# Power.net
KiCad netlist of a schematic drawn in Altium Designer
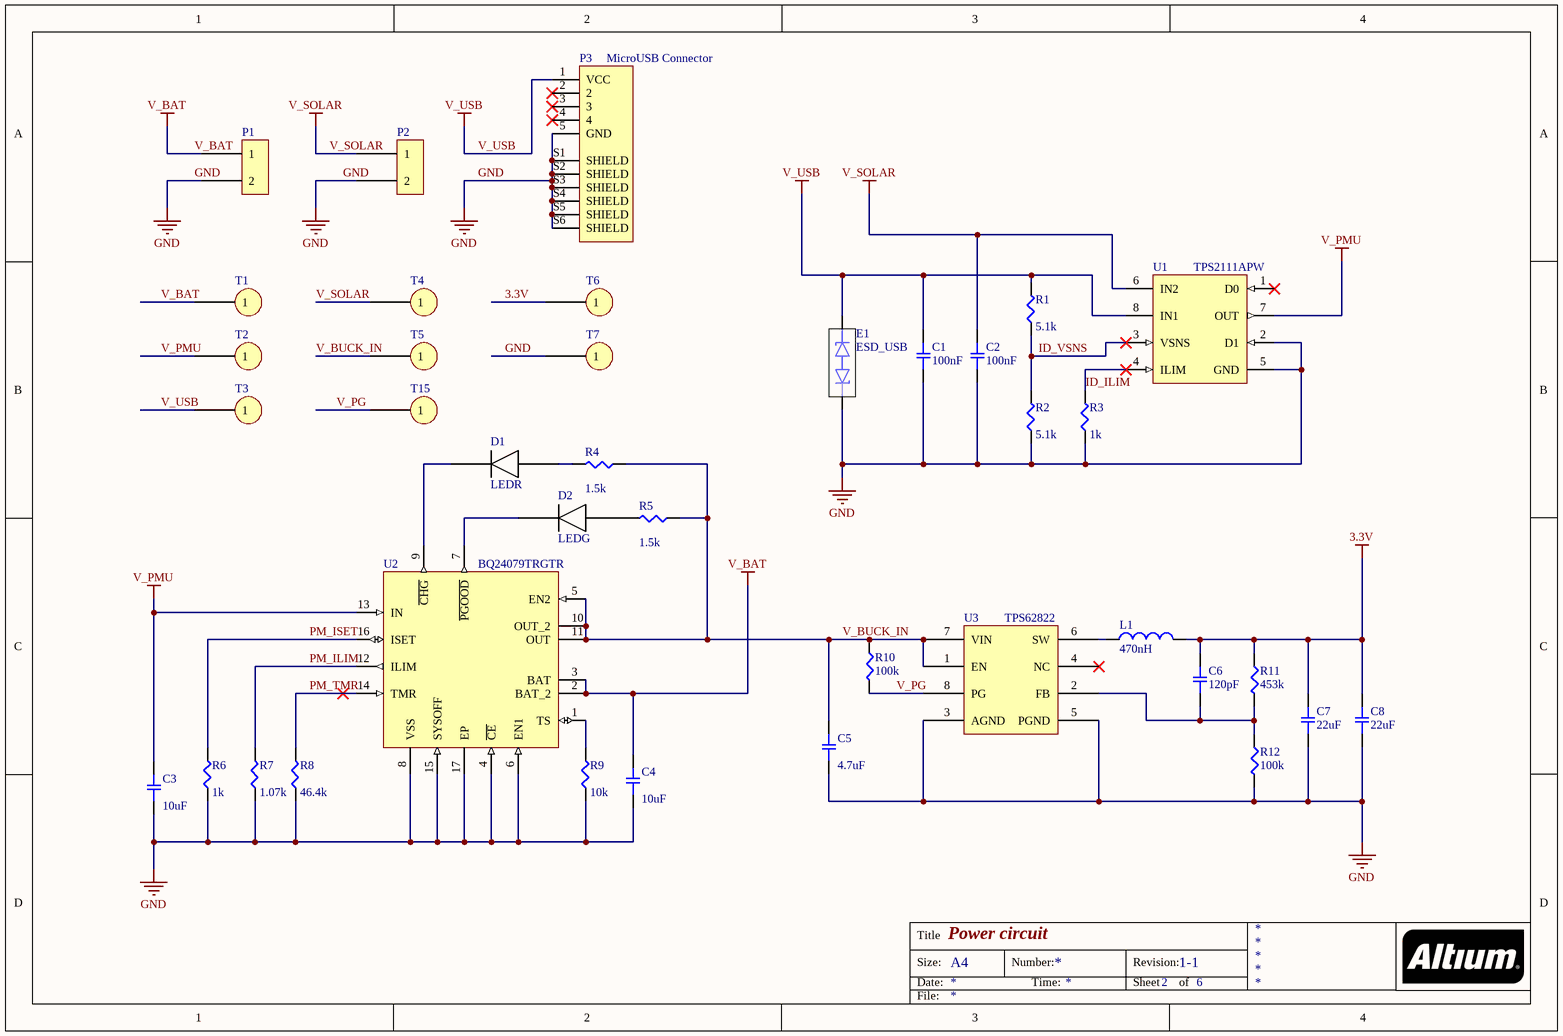
[diagram p0: Power.SchDoc]

(export (version "E")
  (design (tool "Eeschema 10.0.6"))
  (components
    (comp (ref "C1")
      (value "100nF")
      (footprint "1206-CAP")
      (fields (field (name "Comment") "1206C 100NF"))
      (libsource (lib "passive components") (part "1206C 100NF"))
    )
    (comp (ref "C2")
      (value "100nF")
      (footprint "1206-CAP")
      (fields (field (name "Comment") "1206C 100NF"))
      (libsource (lib "passive components") (part "1206C 100NF"))
    )
    (comp (ref "C3")
      (value "10uF")
      (footprint "0805-CAP")
      (fields (field (name "Comment") "0805C 10UF"))
      (libsource (lib "passive components") (part "0805C 10UF"))
    )
    (comp (ref "C4")
      (value "10uF")
      (footprint "0805-CAP")
      (fields (field (name "Comment") "0805C 10UF"))
      (libsource (lib "passive components") (part "0805C 10UF"))
    )
    (comp (ref "C5")
      (value "4.7uF")
      (footprint "0603-CAP")
      (fields (field (name "Comment") "0603C 4U7F"))
      (libsource (lib "passive components") (part "0603C 4U7F"))
    )
    (comp (ref "C6")
      (value "120pF")
      (footprint "0603-CAP")
      (fields (field (name "Comment") "0603C 120PF"))
      (libsource (lib "passive components") (part "0603C 120PF"))
    )
    (comp (ref "C7")
      (value "22uF")
      (footprint "1210-CAP")
      (fields (field (name "Comment") "1210C 22UF"))
      (libsource (lib "passive components") (part "1210C 22UF"))
    )
    (comp (ref "C8")
      (value "22uF")
      (footprint "1210-CAP")
      (fields (field (name "Comment") "1210C 22UF"))
      (libsource (lib "passive components") (part "1210C 22UF"))
    )
    (comp (ref "D1")
      (value "LEDR")
      (footprint "0603-LED")
      (libsource (lib "passive components") (part "0603 LEDR"))
    )
    (comp (ref "D2")
      (value "LEDG")
      (footprint "0603-LED")
      (libsource (lib "passive components") (part "0603 LEDG"))
    )
    (comp (ref "E1")
      (value "ESD_USB")
      (footprint "ESD_USB")
      (libsource (lib "passive components") (part "ESD_USB"))
    )
    (comp (ref "L1")
      (value "470nH")
      (footprint "Inductor 470NH")
      (fields (field (name "Comment") "Inductor 470NH"))
      (libsource (lib "passive components") (part "Inductor 470NH"))
    )
    (comp (ref "P1")
      (value "2pins_connector")
      (footprint "2_PINS_2.54")
      (description "Bat_connector")
      (libsource (lib "2.54_Connectors") (part "2pins_connector"))
    )
    (comp (ref "P2")
      (value "2pins_connector")
      (footprint "2_PINS_2.54")
      (description "Bat_connector")
      (libsource (lib "2.54_Connectors") (part "2pins_connector"))
    )
    (comp (ref "P3")
      (value "MicroUSB Connector")
      (footprint "*HRS_ZX62D-B-5P8_ZX62D-B-5P8(Primary)")
      (description "USB - micro B USB 2.0 Receptacle Connector 5 Position Surface Mount, Right Angle; Through Hole")
      (fields (field (name "MF") "Hirose") (field (name "MP") "ZX62D-B-5P8"))
      (libsource (lib "ZX62D-B-5P8") (part "ZX62D-B-5P8"))
    )
    (comp (ref "R1")
      (value "5.1k")
      (footprint "0805-RES")
      (fields (field (name "Comment") "0805R 5K1R"))
      (libsource (lib "passive components") (part "0805R 5K1R"))
    )
    (comp (ref "R2")
      (value "5.1k")
      (footprint "0805-RES")
      (fields (field (name "Comment") "0805R 5K1R"))
      (libsource (lib "passive components") (part "0805R 5K1R"))
    )
    (comp (ref "R3")
      (value "1k")
      (footprint "0603-RES")
      (fields (field (name "Comment") "0603R 1KR"))
      (libsource (lib "passive components") (part "0603R 1KR"))
    )
    (comp (ref "R4")
      (value "1.5k")
      (footprint "0603-RES")
      (fields (field (name "Comment") "0603R 1K5R"))
      (libsource (lib "passive components") (part "0603R 1K5R"))
    )
    (comp (ref "R5")
      (value "1.5k")
      (footprint "0603-RES")
      (fields (field (name "Comment") "0603R 1K5R"))
      (libsource (lib "passive components") (part "0603R 1K5R"))
    )
    (comp (ref "R6")
      (value "1k")
      (footprint "0603-RES")
      (fields (field (name "Comment") "0603R 1KR"))
      (libsource (lib "passive components") (part "0603R 1KR"))
    )
    (comp (ref "R7")
      (value "1.07k")
      (footprint "0603-RES")
      (fields (field (name "Comment") "0603R 1K07R"))
      (libsource (lib "passive components") (part "0603R 1K07R"))
    )
    (comp (ref "R8")
      (value "46.4k")
      (footprint "0603-RES")
      (fields (field (name "Comment") "0603R 46K4R"))
      (libsource (lib "passive components") (part "0603R 46K4R"))
    )
    (comp (ref "R9")
      (value "10k")
      (footprint "0603-RES")
      (fields (field (name "Comment") "0603R 10KR"))
      (libsource (lib "passive components") (part "0603R 10KR"))
    )
    (comp (ref "R10")
      (value "100k")
      (footprint "0805-RES")
      (fields (field (name "Comment") "0805R 100KR"))
      (libsource (lib "passive components") (part "0805R 100KR"))
    )
    (comp (ref "R11")
      (value "453k")
      (footprint "0805-RES")
      (fields (field (name "Comment") "0805R 453KR"))
      (libsource (lib "passive components") (part "0805R 453KR"))
    )
    (comp (ref "R12")
      (value "100k")
      (footprint "0805-RES")
      (fields (field (name "Comment") "0805R 100KR"))
      (libsource (lib "passive components") (part "0805R 100KR"))
    )
    (comp (ref "T1")
      (value "1pin_header")
      (footprint "1_PIN_2.54")
      (libsource (lib "2.54_Connectors") (part "1pin_header"))
    )
    (comp (ref "T2")
      (value "1pin_header")
      (footprint "1_PIN_2.54")
      (libsource (lib "2.54_Connectors") (part "1pin_header"))
    )
    (comp (ref "T3")
      (value "1pin_header")
      (footprint "1_PIN_2.54")
      (libsource (lib "2.54_Connectors") (part "1pin_header"))
    )
    (comp (ref "T4")
      (value "1pin_header")
      (footprint "1_PIN_2.54")
      (libsource (lib "2.54_Connectors") (part "1pin_header"))
    )
    (comp (ref "T5")
      (value "1pin_header")
      (footprint "1_PIN_2.54")
      (libsource (lib "2.54_Connectors") (part "1pin_header"))
    )
    (comp (ref "T6")
      (value "1pin_header")
      (footprint "1_PIN_2.54")
      (libsource (lib "2.54_Connectors") (part "1pin_header"))
    )
    (comp (ref "T7")
      (value "1pin_header")
      (footprint "1_PIN_2.54")
      (libsource (lib "2.54_Connectors") (part "1pin_header"))
    )
    (comp (ref "T15") (value "*") (footprint "1_PIN_2.54") (libsource (lib "*") (part "1pin_header")))
    (comp (ref "U1")
      (value "TPS2111APW")
      (footprint "*SOP65P640X120-8N")
      (description "OR Controller Source Selector Switch N-Channel 2:1 8-TSSOP")
      (fields (field (name "MF") "Texas Instruments") (field (name "MP") "TPS2110APWR"))
      (libsource (lib "TPS2111APW") (part "TPS2111APW"))
    )
    (comp (ref "U2")
      (value "BQ24079TRGTR")
      (footprint "*QFN50P300X300X100-17N")
      (fields (field (name "MF") "Texas Instruments") (field (name "MP") "BQ24079RGTR"))
      (libsource (lib "BQ24079TRGTR") (part "BQ24079TRGTR"))
    )
    (comp (ref "U3")
      (value "TPS62822")
      (footprint "SON50P150X100_HS-9N")
      (fields (field (name "MF") "Texas Instruments") (field (name "MP") "TPS62822DLCR"))
      (libsource (lib "TPS62822") (part "TPS62822"))
    )
  )
  (nets
    (net (code "1") (name "/ID_ILIM") (class "Default")
      (node (ref "R3") (pin "2") (pinfunction "2_2") (pintype "passive"))
      (node (ref "U1") (pin "4") (pinfunction "ILIM_4") (pintype "input"))
    )
    (net (code "2") (name "/ID_VSNS") (class "Default")
      (node (ref "R1") (pin "1") (pinfunction "1_1") (pintype "passive"))
      (node (ref "R2") (pin "2") (pinfunction "2_2") (pintype "passive"))
      (node (ref "U1") (pin "3") (pinfunction "VSNS_3") (pintype "input"))
    )
    (net (code "3") (name "/PM_ILIM") (class "Default")
      (node (ref "R7") (pin "2") (pinfunction "2_2") (pintype "passive"))
      (node (ref "U2") (pin "12") (pinfunction "ILIM_12") (pintype "output"))
    )
    (net (code "4") (name "/PM_ISET") (class "Default")
      (node (ref "R6") (pin "2") (pinfunction "2_2") (pintype "passive"))
      (node (ref "U2") (pin "16") (pinfunction "ISET_16") (pintype "bidirectional"))
    )
    (net (code "5") (name "/PM_TMR") (class "Default")
      (node (ref "R8") (pin "2") (pinfunction "2_2") (pintype "passive"))
      (node (ref "U2") (pin "14") (pinfunction "TMR_14") (pintype "input"))
    )
    (net (code "6") (name "/V_BUCK_IN") (class "Default")
      (node (ref "C5") (pin "2") (pinfunction "2_2") (pintype "passive"))
      (node (ref "R10") (pin "1") (pinfunction "1_1") (pintype "passive"))
      (node (ref "R4") (pin "1") (pinfunction "1_1") (pintype "passive"))
      (node (ref "R5") (pin "1") (pinfunction "1_1") (pintype "passive"))
      (node (ref "T5") (pin "1") (pinfunction "1_1") (pintype "passive"))
      (node (ref "U2") (pin "10") (pinfunction "OUT_2_10") (pintype "power_in"))
      (node (ref "U2") (pin "11") (pinfunction "OUT_11") (pintype "power_in"))
      (node (ref "U2") (pin "5") (pinfunction "EN2_5") (pintype "input"))
      (node (ref "U3") (pin "1") (pinfunction "EN_1") (pintype "passive"))
      (node (ref "U3") (pin "7") (pinfunction "VIN_7") (pintype "passive"))
    )
    (net (code "7") (name "/V_PG") (class "Default")
      (node (ref "R10") (pin "2") (pinfunction "2_2") (pintype "passive"))
      (node (ref "T15") (pin "1") (pinfunction "1_1") (pintype "passive"))
      (node (ref "U3") (pin "8") (pinfunction "PG_8") (pintype "passive"))
    )
    (net (code "8") (name "3.3V") (class "Default")
      (node (ref "C6") (pin "2") (pinfunction "2_2") (pintype "passive"))
      (node (ref "C7") (pin "2") (pinfunction "2_2") (pintype "passive"))
      (node (ref "C8") (pin "2") (pinfunction "2_2") (pintype "passive"))
      (node (ref "L1") (pin "2") (pinfunction "2_2") (pintype "passive"))
      (node (ref "R11") (pin "1") (pinfunction "1_1") (pintype "passive"))
      (node (ref "T6") (pin "1") (pinfunction "1_1") (pintype "passive"))
    )
    (net (code "9") (name "GND") (class "Default")
      (node (ref "C1") (pin "1") (pinfunction "1_1") (pintype "passive"))
      (node (ref "C2") (pin "1") (pinfunction "1_1") (pintype "passive"))
      (node (ref "C3") (pin "1") (pinfunction "1_1") (pintype "passive"))
      (node (ref "C4") (pin "1") (pinfunction "1_1") (pintype "passive"))
      (node (ref "C5") (pin "1") (pinfunction "1_1") (pintype "passive"))
      (node (ref "C7") (pin "1") (pinfunction "1_1") (pintype "passive"))
      (node (ref "C8") (pin "1") (pinfunction "1_1") (pintype "passive"))
      (node (ref "E1") (pin "1") (pinfunction "1_1") (pintype "passive"))
      (node (ref "P1") (pin "2") (pinfunction "2_2") (pintype "passive"))
      (node (ref "P2") (pin "2") (pinfunction "2_2") (pintype "passive"))
      (node (ref "P3") (pin "5") (pinfunction "GND_5") (pintype "passive"))
      (node (ref "P3") (pin "S1") (pinfunction "SHIELD_S1") (pintype "passive"))
      (node (ref "P3") (pin "S2") (pinfunction "SHIELD_S2") (pintype "passive"))
      (node (ref "P3") (pin "S3") (pinfunction "SHIELD_S3") (pintype "passive"))
      (node (ref "P3") (pin "S4") (pinfunction "SHIELD_S4") (pintype "passive"))
      (node (ref "P3") (pin "S5") (pinfunction "SHIELD_S5") (pintype "passive"))
      (node (ref "P3") (pin "S6") (pinfunction "SHIELD_S6") (pintype "passive"))
      (node (ref "R12") (pin "2") (pinfunction "2_2") (pintype "passive"))
      (node (ref "R2") (pin "1") (pinfunction "1_1") (pintype "passive"))
      (node (ref "R3") (pin "1") (pinfunction "1_1") (pintype "passive"))
      (node (ref "R6") (pin "1") (pinfunction "1_1") (pintype "passive"))
      (node (ref "R7") (pin "1") (pinfunction "1_1") (pintype "passive"))
      (node (ref "R8") (pin "1") (pinfunction "1_1") (pintype "passive"))
      (node (ref "R9") (pin "1") (pinfunction "1_1") (pintype "passive"))
      (node (ref "T7") (pin "1") (pinfunction "1_1") (pintype "passive"))
      (node (ref "U1") (pin "2") (pinfunction "D1_2") (pintype "input"))
      (node (ref "U1") (pin "5") (pinfunction "GND_5") (pintype "passive"))
      (node (ref "U2") (pin "15") (pinfunction "SYSOFF_15") (pintype "input"))
      (node (ref "U2") (pin "17") (pinfunction "EP_17") (pintype "passive"))
      (node (ref "U2") (pin "4") (pinfunction "~{CE}_4") (pintype "input"))
      (node (ref "U2") (pin "6") (pinfunction "EN1_6") (pintype "input"))
      (node (ref "U2") (pin "8") (pinfunction "VSS_8") (pintype "passive"))
      (node (ref "U3") (pin "3") (pinfunction "AGND_3") (pintype "passive"))
      (node (ref "U3") (pin "5") (pinfunction "PGND_5") (pintype "passive"))
    )
    (net (code "10") (name "Net-(D1-Pad1)") (class "Default")
      (node (ref "D1") (pin "1") (pinfunction "1_1") (pintype "passive"))
      (node (ref "R4") (pin "2") (pinfunction "2_2") (pintype "passive"))
    )
    (net (code "11") (name "Net-(D2-Pad1)") (class "Default")
      (node (ref "D2") (pin "1") (pinfunction "1_1") (pintype "passive"))
      (node (ref "R5") (pin "2") (pinfunction "2_2") (pintype "passive"))
    )
    (net (code "12") (name "Net-(U2-TS)") (class "Default")
      (node (ref "R9") (pin "2") (pinfunction "2_2") (pintype "passive"))
      (node (ref "U2") (pin "1") (pinfunction "TS_1") (pintype "bidirectional"))
    )
    (net (code "13") (name "Net-(U2-~{CHG})") (class "Default")
      (node (ref "D1") (pin "2") (pinfunction "2_2") (pintype "passive"))
      (node (ref "U2") (pin "9") (pinfunction "~{CHG}_9") (pintype "output"))
    )
    (net (code "14") (name "Net-(U2-~{PGOOD})") (class "Default")
      (node (ref "D2") (pin "2") (pinfunction "2_2") (pintype "passive"))
      (node (ref "U2") (pin "7") (pinfunction "~{PGOOD}_7") (pintype "output"))
    )
    (net (code "15") (name "Net-(U3-FB)") (class "Default")
      (node (ref "C6") (pin "1") (pinfunction "1_1") (pintype "passive"))
      (node (ref "R11") (pin "2") (pinfunction "2_2") (pintype "passive"))
      (node (ref "R12") (pin "1") (pinfunction "1_1") (pintype "passive"))
      (node (ref "U3") (pin "2") (pinfunction "FB_2") (pintype "passive"))
    )
    (net (code "16") (name "Net-(U3-SW)") (class "Default")
      (node (ref "L1") (pin "1") (pinfunction "1_1") (pintype "passive"))
      (node (ref "U3") (pin "6") (pinfunction "SW_6") (pintype "passive"))
    )
    (net (code "17") (name "V_BAT") (class "Default")
      (node (ref "C4") (pin "2") (pinfunction "2_2") (pintype "passive"))
      (node (ref "P1") (pin "1") (pinfunction "1_1") (pintype "passive"))
      (node (ref "T1") (pin "1") (pinfunction "1_1") (pintype "passive"))
      (node (ref "U2") (pin "2") (pinfunction "BAT_2_2") (pintype "power_in"))
      (node (ref "U2") (pin "3") (pinfunction "BAT_3") (pintype "power_in"))
    )
    (net (code "18") (name "V_PMU") (class "Default")
      (node (ref "C3") (pin "2") (pinfunction "2_2") (pintype "passive"))
      (node (ref "T2") (pin "1") (pinfunction "1_1") (pintype "passive"))
      (node (ref "U1") (pin "7") (pinfunction "OUT_7") (pintype "output"))
      (node (ref "U2") (pin "13") (pinfunction "IN_13") (pintype "input"))
    )
    (net (code "19") (name "V_SOLAR") (class "Default")
      (node (ref "C2") (pin "2") (pinfunction "2_2") (pintype "passive"))
      (node (ref "P2") (pin "1") (pinfunction "1_1") (pintype "passive"))
      (node (ref "T4") (pin "1") (pinfunction "1_1") (pintype "passive"))
      (node (ref "U1") (pin "6") (pinfunction "IN2_6") (pintype "power_in"))
    )
    (net (code "20") (name "V_USB") (class "Default")
      (node (ref "C1") (pin "2") (pinfunction "2_2") (pintype "passive"))
      (node (ref "E1") (pin "2") (pinfunction "2_2") (pintype "passive"))
      (node (ref "P3") (pin "1") (pinfunction "VCC_1") (pintype "passive"))
      (node (ref "R1") (pin "2") (pinfunction "2_2") (pintype "passive"))
      (node (ref "T3") (pin "1") (pinfunction "1_1") (pintype "passive"))
      (node (ref "U1") (pin "8") (pinfunction "IN1_8") (pintype "power_in"))
    )
    (net (code "21") (name "unconnected-(P3-Pad2)") (class "Default")
      (node (ref "P3") (pin "2") (pinfunction "2_2") (pintype "passive+no_connect"))
    )
    (net (code "22") (name "unconnected-(P3-Pad3)") (class "Default")
      (node (ref "P3") (pin "3") (pinfunction "3_3") (pintype "passive+no_connect"))
    )
    (net (code "23") (name "unconnected-(P3-Pad4)") (class "Default")
      (node (ref "P3") (pin "4") (pinfunction "4_4") (pintype "passive+no_connect"))
    )
    (net (code "24") (name "unconnected-(U1-D0-Pad1)") (class "Default")
      (node (ref "U1") (pin "1") (pinfunction "D0_1") (pintype "input+no_connect"))
    )
    (net (code "25") (name "unconnected-(U3-NC-Pad4)") (class "Default")
      (node (ref "U3") (pin "4") (pinfunction "NC_4") (pintype "passive+no_connect"))
    )
  )
)
